# timer_countdown_two.net
KiCad netlist of a schematic drawn in EAGLE
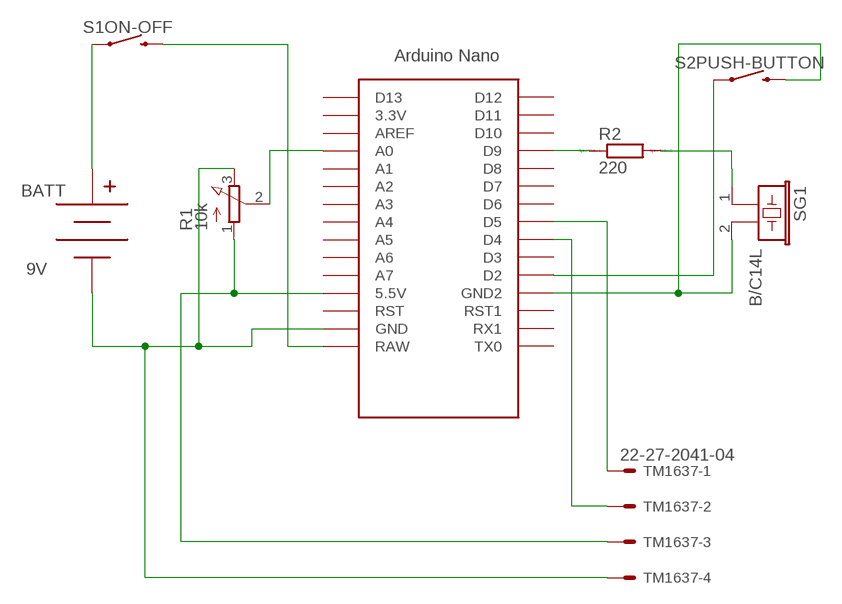
[diagram p0: schematic, sheet 1]

(export (version "E")
  (design (tool "Eeschema 10.0.6"))
  (components
    (comp (ref "BATT")
      (value "9V")
      (footprint "eagle-import:BC9VPC")
      (libsource (lib "eagle-import") (part "BC9VPC"))
    )
    (comp (ref "R1")
      (value "10k")
      (footprint "eagle-import:3RP_1610N")
      (libsource (lib "eagle-import") (part "3RP/1610N"))
    )
    (comp (ref "R2")
      (value "220")
      (footprint "eagle-import:0204_7")
      (libsource (lib "eagle-import") (part "R0204/7"))
    )
    (comp (ref "S1ON-OFF")
      (value "MOMENTARY-SWITCH-SPST-PTH-6.0MM")
      (footprint "eagle-import:TACTILE_SWITCH_PTH_6.0MM")
      (libsource (lib "eagle-import") (part "MOMENTARY-SWITCH-SPST-PTH-6.0MM"))
    )
    (comp (ref "S2PUSH-BUTTON")
      (value "MOMENTARY-SWITCH-SPST-PTH-6.0MM")
      (footprint "eagle-import:TACTILE_SWITCH_PTH_6.0MM")
      (libsource (lib "eagle-import") (part "MOMENTARY-SWITCH-SPST-PTH-6.0MM"))
    )
    (comp (ref "SG1")
      (value "B/C14L")
      (footprint "eagle-import:B_C14L")
      (libsource (lib "eagle-import") (part "B/C14L"))
    )
    (comp (ref "TM1637")
      (value "22-27-2041-04")
      (footprint "eagle-import:6410-04")
      (fields (field (name "MF") "MOLEX"))
      (libsource (lib "eagle-import") (part "22-?-0427-2041"))
    )
    (comp (ref "U$1")
      (value "NANO")
      (footprint "eagle-import:NANO")
      (libsource (lib "eagle-import") (part "NANO"))
    )
  )
  (nets
    (net (code "1") (name "Net-(BATT-PadV+)") (class "Default")
      (node (ref "BATT") (pin "V+") (pinfunction "V+_V+") (pintype "bidirectional"))
      (node (ref "S1ON-OFF") (pin "1") (pinfunction "1_1") (pintype "passive"))
    )
    (net (code "2") (name "Net-(R1-A)") (class "Default")
      (node (ref "R1") (pin "1") (pinfunction "A_1") (pintype "passive"))
      (node (ref "TM1637") (pin "3") (pinfunction "S_3") (pintype "passive"))
      (node (ref "U$1") (pin "5V") (pinfunction "5.5V_5V") (pintype "bidirectional"))
    )
    (net (code "3") (name "Net-(R1-E)") (class "Default")
      (node (ref "BATT") (pin "V-") (pinfunction "V-_V-") (pintype "bidirectional"))
      (node (ref "R1") (pin "3") (pinfunction "E_3") (pintype "passive"))
      (node (ref "TM1637") (pin "4") (pinfunction "S_4") (pintype "passive"))
      (node (ref "U$1") (pin "GND") (pinfunction "GND_GND") (pintype "bidirectional"))
    )
    (net (code "4") (name "Net-(R1-S)") (class "Default")
      (node (ref "R1") (pin "2") (pinfunction "S_2") (pintype "passive"))
      (node (ref "U$1") (pin "A0") (pinfunction "A0_A0") (pintype "bidirectional"))
    )
    (net (code "5") (name "Net-(R2-Pad1)") (class "Default")
      (node (ref "R2") (pin "1") (pinfunction "1_1") (pintype "passive"))
      (node (ref "U$1") (pin "D9") (pinfunction "D9_D9") (pintype "bidirectional"))
    )
    (net (code "6") (name "Net-(R2-Pad2)") (class "Default")
      (node (ref "R2") (pin "2") (pinfunction "2_2") (pintype "passive"))
      (node (ref "SG1") (pin "1") (pinfunction "1_1") (pintype "passive"))
    )
    (net (code "7") (name "Net-(S1ON-OFF-2)") (class "Default")
      (node (ref "S1ON-OFF") (pin "3") (pinfunction "2_3") (pintype "passive"))
      (node (ref "U$1") (pin "RAW") (pinfunction "RAW_RAW") (pintype "bidirectional"))
    )
    (net (code "8") (name "Net-(S2PUSH-BUTTON-2)") (class "Default")
      (node (ref "S2PUSH-BUTTON") (pin "3") (pinfunction "2_3") (pintype "passive"))
      (node (ref "SG1") (pin "2") (pinfunction "2_2") (pintype "passive"))
      (node (ref "U$1") (pin "GND1") (pinfunction "GND2_GND1") (pintype "bidirectional"))
    )
    (net (code "9") (name "Net-(S2PUSH-BUTTON-Pad1)") (class "Default")
      (node (ref "S2PUSH-BUTTON") (pin "1") (pinfunction "1_1") (pintype "passive"))
      (node (ref "U$1") (pin "D2") (pinfunction "D2_D2") (pintype "bidirectional"))
    )
    (net (code "10") (name "Net-(TM1637A-S)") (class "Default")
      (node (ref "TM1637") (pin "1") (pinfunction "S_1") (pintype "passive"))
      (node (ref "U$1") (pin "D5") (pinfunction "D5_D5") (pintype "bidirectional"))
    )
    (net (code "11") (name "Net-(TM1637B-S)") (class "Default")
      (node (ref "TM1637") (pin "2") (pinfunction "S_2") (pintype "passive"))
      (node (ref "U$1") (pin "D4") (pinfunction "D4_D4") (pintype "bidirectional"))
    )
    (net (code "12") (name "unconnected-(U$1-Pad3.3V)") (class "Default")
      (node (ref "U$1") (pin "3.3V") (pinfunction "3.3V_3.3V") (pintype "bidirectional"))
    )
    (net (code "13") (name "unconnected-(U$1-PadA1)") (class "Default")
      (node (ref "U$1") (pin "A1") (pinfunction "A1_A1") (pintype "bidirectional"))
    )
    (net (code "14") (name "unconnected-(U$1-PadA2)") (class "Default")
      (node (ref "U$1") (pin "A2") (pinfunction "A2_A2") (pintype "bidirectional"))
    )
    (net (code "15") (name "unconnected-(U$1-PadA3)") (class "Default")
      (node (ref "U$1") (pin "A3") (pinfunction "A3_A3") (pintype "bidirectional"))
    )
    (net (code "16") (name "unconnected-(U$1-PadA4)") (class "Default")
      (node (ref "U$1") (pin "A4") (pinfunction "A4_A4") (pintype "bidirectional"))
    )
    (net (code "17") (name "unconnected-(U$1-PadA5)") (class "Default")
      (node (ref "U$1") (pin "A5") (pinfunction "A5_A5") (pintype "bidirectional"))
    )
    (net (code "18") (name "unconnected-(U$1-PadA6)") (class "Default")
      (node (ref "U$1") (pin "A6") (pinfunction "A6_A6") (pintype "bidirectional"))
    )
    (net (code "19") (name "unconnected-(U$1-PadA7)") (class "Default")
      (node (ref "U$1") (pin "A7") (pinfunction "A7_A7") (pintype "bidirectional"))
    )
    (net (code "20") (name "unconnected-(U$1-PadAREF)") (class "Default")
      (node (ref "U$1") (pin "AREF") (pinfunction "AREF_AREF") (pintype "bidirectional"))
    )
    (net (code "21") (name "unconnected-(U$1-PadD3)") (class "Default")
      (node (ref "U$1") (pin "D3") (pinfunction "D3_D3") (pintype "bidirectional"))
    )
    (net (code "22") (name "unconnected-(U$1-PadD6)") (class "Default")
      (node (ref "U$1") (pin "D6") (pinfunction "D6_D6") (pintype "bidirectional"))
    )
    (net (code "23") (name "unconnected-(U$1-PadD7)") (class "Default")
      (node (ref "U$1") (pin "D7") (pinfunction "D7_D7") (pintype "bidirectional"))
    )
    (net (code "24") (name "unconnected-(U$1-PadD8)") (class "Default")
      (node (ref "U$1") (pin "D8") (pinfunction "D8_D8") (pintype "bidirectional"))
    )
    (net (code "25") (name "unconnected-(U$1-PadD10)") (class "Default")
      (node (ref "U$1") (pin "D10") (pinfunction "D10_D10") (pintype "bidirectional"))
    )
    (net (code "26") (name "unconnected-(U$1-PadD11)") (class "Default")
      (node (ref "U$1") (pin "D11") (pinfunction "D11_D11") (pintype "bidirectional"))
    )
    (net (code "27") (name "unconnected-(U$1-PadD12)") (class "Default")
      (node (ref "U$1") (pin "D12") (pinfunction "D12_D12") (pintype "bidirectional"))
    )
    (net (code "28") (name "unconnected-(U$1-PadD13)") (class "Default")
      (node (ref "U$1") (pin "D13") (pinfunction "D13_D13") (pintype "bidirectional"))
    )
    (net (code "29") (name "unconnected-(U$1-PadICSP1)") (class "Default")
      (node (ref "U$1") (pin "ICSP1") (pinfunction "ICSP1_ICSP1") (pintype "bidirectional"))
    )
    (net (code "30") (name "unconnected-(U$1-PadICSP2)") (class "Default")
      (node (ref "U$1") (pin "ICSP2") (pinfunction "ICSP2_ICSP2") (pintype "bidirectional"))
    )
    (net (code "31") (name "unconnected-(U$1-PadICSP3)") (class "Default")
      (node (ref "U$1") (pin "ICSP3") (pinfunction "ICSP3_ICSP3") (pintype "bidirectional"))
    )
    (net (code "32") (name "unconnected-(U$1-PadICSP4)") (class "Default")
      (node (ref "U$1") (pin "ICSP4") (pinfunction "ICSP4_ICSP4") (pintype "bidirectional"))
    )
    (net (code "33") (name "unconnected-(U$1-PadICSP5)") (class "Default")
      (node (ref "U$1") (pin "ICSP5") (pinfunction "ICSP5_ICSP5") (pintype "bidirectional"))
    )
    (net (code "34") (name "unconnected-(U$1-PadICSP6)") (class "Default")
      (node (ref "U$1") (pin "ICSP6") (pinfunction "ICSP6_ICSP6") (pintype "bidirectional"))
    )
    (net (code "35") (name "unconnected-(U$1-PadRST)") (class "Default")
      (node (ref "U$1") (pin "RST") (pinfunction "RST_RST") (pintype "bidirectional"))
    )
    (net (code "36") (name "unconnected-(U$1-PadRST1)") (class "Default")
      (node (ref "U$1") (pin "RST1") (pinfunction "RST1_RST1") (pintype "bidirectional"))
    )
    (net (code "37") (name "unconnected-(U$1-PadRX1)") (class "Default")
      (node (ref "U$1") (pin "RX1") (pinfunction "RX1_RX1") (pintype "bidirectional"))
    )
    (net (code "38") (name "unconnected-(U$1-PadTX0)") (class "Default")
      (node (ref "U$1") (pin "TX0") (pinfunction "TX0_TX0") (pintype "bidirectional"))
    )
  )
)
